# 03_01_MCU_ESP32_Interface.net
KiCad netlist of a schematic drawn in Altium Designer
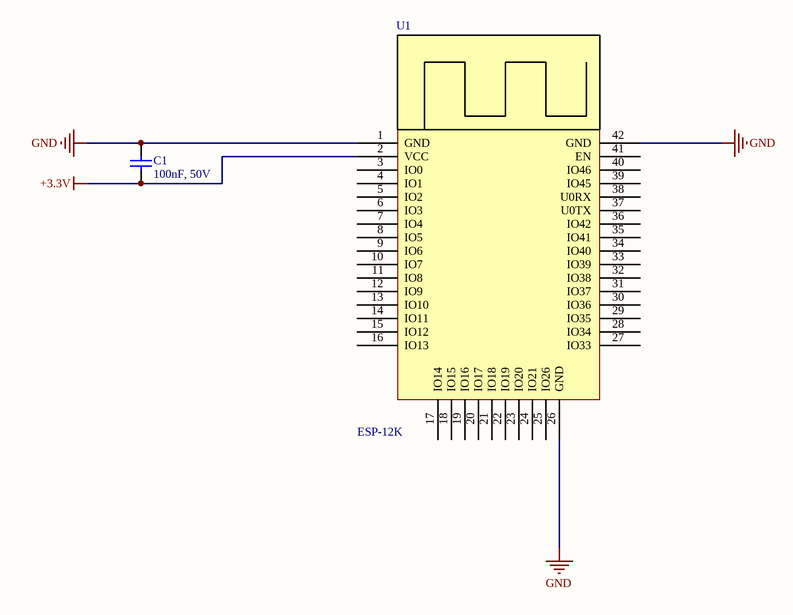
[diagram p0: 03_01_MCU_ESP32_Interface.SchDoc]

(export (version "E")
  (design (tool "Eeschema 10.0.6"))
  (components
    (comp (ref "C1")
      (value "100nF, 50V")
      (footprint "WCAP-CSGP_0603_H=0.8mm_Reflow")
      (description "WCAP-CSGP Multilayer Ceramic Chip Capacitor, General Purpose, size 0603, X7R, 100nF, 50V")
      (fields
        (field (name "MANUFACTURER PART NUMBER") "885012206095")
        (field (name "MANUFACTURER") "Wurth Elektronik")
      )
      (libsource (lib "Altium_WCAP-CSGP (rev20a)") (part "885012206095"))
    )
    (comp (ref "U1")
      (value "ESP-12K")
      (footprint "CAC-150P3100X1800-41N")
      (description "ESP32-S2")
      (libsource (lib "MiclsLib") (part "ESP-12K"))
    )
  )
  (nets
    (net (code "1") (name "+3.3V") (class "Default")
      (node (ref "C1") (pin "1") (pinfunction "1_1") (pintype "passive"))
      (node (ref "U1") (pin "2") (pinfunction "VCC_2") (pintype "passive"))
    )
    (net (code "2") (name "GND") (class "Default")
      (node (ref "C1") (pin "2") (pinfunction "2_2") (pintype "passive"))
      (node (ref "U1") (pin "1") (pinfunction "GND_1") (pintype "passive"))
      (node (ref "U1") (pin "26") (pinfunction "GND_26") (pintype "passive"))
      (node (ref "U1") (pin "42") (pinfunction "GND_42") (pintype "passive"))
    )
    (net (code "3") (name "unconnected-(U1-EN-Pad41)") (class "Default")
      (node (ref "U1") (pin "41") (pinfunction "EN_41") (pintype "passive"))
    )
    (net (code "4") (name "unconnected-(U1-IO0-Pad3)") (class "Default")
      (node (ref "U1") (pin "3") (pinfunction "IO0_3") (pintype "passive"))
    )
    (net (code "5") (name "unconnected-(U1-IO1-Pad4)") (class "Default")
      (node (ref "U1") (pin "4") (pinfunction "IO1_4") (pintype "passive"))
    )
    (net (code "6") (name "unconnected-(U1-IO2-Pad5)") (class "Default")
      (node (ref "U1") (pin "5") (pinfunction "IO2_5") (pintype "passive"))
    )
    (net (code "7") (name "unconnected-(U1-IO3-Pad6)") (class "Default")
      (node (ref "U1") (pin "6") (pinfunction "IO3_6") (pintype "passive"))
    )
    (net (code "8") (name "unconnected-(U1-IO4-Pad7)") (class "Default")
      (node (ref "U1") (pin "7") (pinfunction "IO4_7") (pintype "passive"))
    )
    (net (code "9") (name "unconnected-(U1-IO5-Pad8)") (class "Default")
      (node (ref "U1") (pin "8") (pinfunction "IO5_8") (pintype "passive"))
    )
    (net (code "10") (name "unconnected-(U1-IO6-Pad9)") (class "Default")
      (node (ref "U1") (pin "9") (pinfunction "IO6_9") (pintype "passive"))
    )
    (net (code "11") (name "unconnected-(U1-IO7-Pad10)") (class "Default")
      (node (ref "U1") (pin "10") (pinfunction "IO7_10") (pintype "passive"))
    )
    (net (code "12") (name "unconnected-(U1-IO8-Pad11)") (class "Default")
      (node (ref "U1") (pin "11") (pinfunction "IO8_11") (pintype "passive"))
    )
    (net (code "13") (name "unconnected-(U1-IO9-Pad12)") (class "Default")
      (node (ref "U1") (pin "12") (pinfunction "IO9_12") (pintype "passive"))
    )
    (net (code "14") (name "unconnected-(U1-IO10-Pad13)") (class "Default")
      (node (ref "U1") (pin "13") (pinfunction "IO10_13") (pintype "passive"))
    )
    (net (code "15") (name "unconnected-(U1-IO11-Pad14)") (class "Default")
      (node (ref "U1") (pin "14") (pinfunction "IO11_14") (pintype "passive"))
    )
    (net (code "16") (name "unconnected-(U1-IO12-Pad15)") (class "Default")
      (node (ref "U1") (pin "15") (pinfunction "IO12_15") (pintype "passive"))
    )
    (net (code "17") (name "unconnected-(U1-IO13-Pad16)") (class "Default")
      (node (ref "U1") (pin "16") (pinfunction "IO13_16") (pintype "passive"))
    )
    (net (code "18") (name "unconnected-(U1-IO14-Pad17)") (class "Default")
      (node (ref "U1") (pin "17") (pinfunction "IO14_17") (pintype "passive"))
    )
    (net (code "19") (name "unconnected-(U1-IO15-Pad18)") (class "Default")
      (node (ref "U1") (pin "18") (pinfunction "IO15_18") (pintype "passive"))
    )
    (net (code "20") (name "unconnected-(U1-IO16-Pad19)") (class "Default")
      (node (ref "U1") (pin "19") (pinfunction "IO16_19") (pintype "passive"))
    )
    (net (code "21") (name "unconnected-(U1-IO17-Pad20)") (class "Default")
      (node (ref "U1") (pin "20") (pinfunction "IO17_20") (pintype "passive"))
    )
    (net (code "22") (name "unconnected-(U1-IO18-Pad21)") (class "Default")
      (node (ref "U1") (pin "21") (pinfunction "IO18_21") (pintype "passive"))
    )
    (net (code "23") (name "unconnected-(U1-IO19-Pad22)") (class "Default")
      (node (ref "U1") (pin "22") (pinfunction "IO19_22") (pintype "passive"))
    )
    (net (code "24") (name "unconnected-(U1-IO20-Pad23)") (class "Default")
      (node (ref "U1") (pin "23") (pinfunction "IO20_23") (pintype "passive"))
    )
    (net (code "25") (name "unconnected-(U1-IO21-Pad24)") (class "Default")
      (node (ref "U1") (pin "24") (pinfunction "IO21_24") (pintype "passive"))
    )
    (net (code "26") (name "unconnected-(U1-IO26-Pad25)") (class "Default")
      (node (ref "U1") (pin "25") (pinfunction "IO26_25") (pintype "passive"))
    )
    (net (code "27") (name "unconnected-(U1-IO33-Pad27)") (class "Default")
      (node (ref "U1") (pin "27") (pinfunction "IO33_27") (pintype "passive"))
    )
    (net (code "28") (name "unconnected-(U1-IO34-Pad28)") (class "Default")
      (node (ref "U1") (pin "28") (pinfunction "IO34_28") (pintype "passive"))
    )
    (net (code "29") (name "unconnected-(U1-IO35-Pad29)") (class "Default")
      (node (ref "U1") (pin "29") (pinfunction "IO35_29") (pintype "passive"))
    )
    (net (code "30") (name "unconnected-(U1-IO36-Pad30)") (class "Default")
      (node (ref "U1") (pin "30") (pinfunction "IO36_30") (pintype "passive"))
    )
    (net (code "31") (name "unconnected-(U1-IO37-Pad31)") (class "Default")
      (node (ref "U1") (pin "31") (pinfunction "IO37_31") (pintype "passive"))
    )
    (net (code "32") (name "unconnected-(U1-IO38-Pad32)") (class "Default")
      (node (ref "U1") (pin "32") (pinfunction "IO38_32") (pintype "passive"))
    )
    (net (code "33") (name "unconnected-(U1-IO39-Pad33)") (class "Default")
      (node (ref "U1") (pin "33") (pinfunction "IO39_33") (pintype "passive"))
    )
    (net (code "34") (name "unconnected-(U1-IO40-Pad34)") (class "Default")
      (node (ref "U1") (pin "34") (pinfunction "IO40_34") (pintype "passive"))
    )
    (net (code "35") (name "unconnected-(U1-IO41-Pad35)") (class "Default")
      (node (ref "U1") (pin "35") (pinfunction "IO41_35") (pintype "passive"))
    )
    (net (code "36") (name "unconnected-(U1-IO42-Pad36)") (class "Default")
      (node (ref "U1") (pin "36") (pinfunction "IO42_36") (pintype "passive"))
    )
    (net (code "37") (name "unconnected-(U1-IO45-Pad39)") (class "Default")
      (node (ref "U1") (pin "39") (pinfunction "IO45_39") (pintype "passive"))
    )
    (net (code "38") (name "unconnected-(U1-IO46-Pad40)") (class "Default")
      (node (ref "U1") (pin "40") (pinfunction "IO46_40") (pintype "passive"))
    )
    (net (code "39") (name "unconnected-(U1-U0RX-Pad38)") (class "Default")
      (node (ref "U1") (pin "38") (pinfunction "U0RX_38") (pintype "passive"))
    )
    (net (code "40") (name "unconnected-(U1-U0TX-Pad37)") (class "Default")
      (node (ref "U1") (pin "37") (pinfunction "U0TX_37") (pintype "passive"))
    )
  )
)
